# I2C_4CH_PWM_MODULE.net
KiCad netlist of a schematic drawn in EAGLE
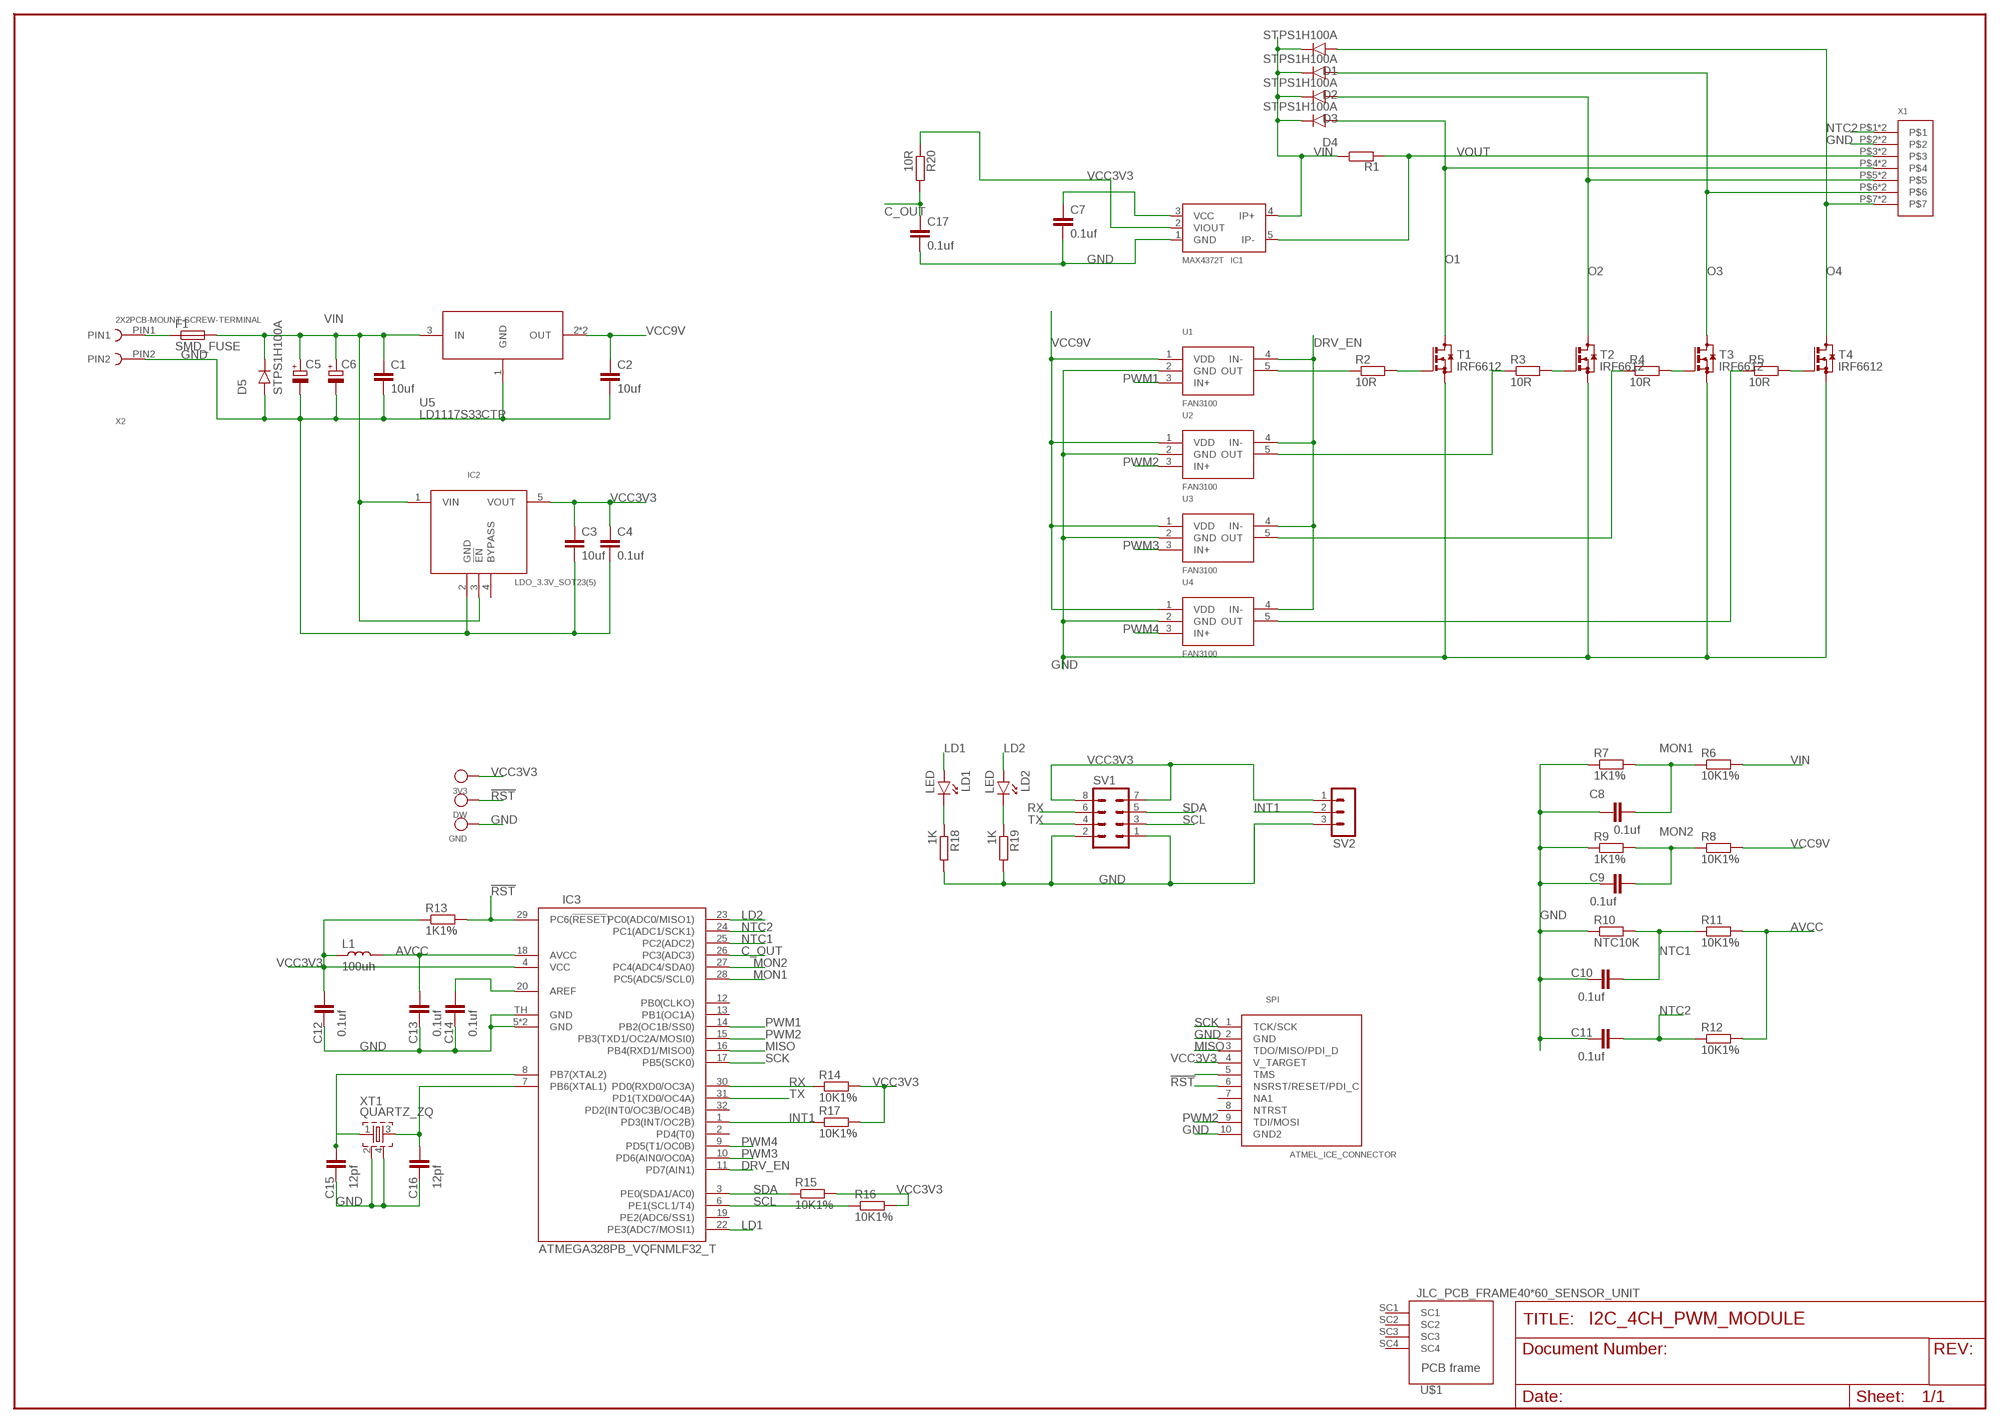
[diagram p0: schematic, sheet 1]

(export (version "E")
  (design (tool "Eeschema 10.0.6"))
  (components
    (comp (ref "3V3")
      (value "TEST_POINT_D2MM")
      (footprint "eagle-import:TP")
      (libsource (lib "eagle-import") (part "TEST_POINT_D2MM"))
    )
    (comp (ref "C1")
      (value "10uf")
      (footprint "eagle-import:1206")
      (libsource (lib "eagle-import") (part "SMD_C1206"))
    )
    (comp (ref "C2")
      (value "10uf")
      (footprint "eagle-import:1206")
      (libsource (lib "eagle-import") (part "SMD_C1206"))
    )
    (comp (ref "C3")
      (value "10uf")
      (footprint "eagle-import:1206")
      (libsource (lib "eagle-import") (part "SMD_C1206"))
    )
    (comp (ref "C4")
      (value "0.1uf")
      (footprint "eagle-import:0603")
      (libsource (lib "eagle-import") (part "SMD_C0603"))
    )
    (comp (ref "C5")
      (value "CPOL-EU153CLV-0605")
      (footprint "eagle-import:153CLV-0605")
      (libsource (lib "eagle-import") (part "CPOL-EU153CLV-0605"))
    )
    (comp (ref "C6")
      (value "CPOL-EU153CLV-0605")
      (footprint "eagle-import:153CLV-0605")
      (libsource (lib "eagle-import") (part "CPOL-EU153CLV-0605"))
    )
    (comp (ref "C7")
      (value "0.1uf")
      (footprint "eagle-import:0603")
      (libsource (lib "eagle-import") (part "SMD_C0603"))
    )
    (comp (ref "C8")
      (value "0.1uf")
      (footprint "eagle-import:0603")
      (libsource (lib "eagle-import") (part "SMD_C0603"))
    )
    (comp (ref "C9")
      (value "0.1uf")
      (footprint "eagle-import:0603")
      (libsource (lib "eagle-import") (part "SMD_C0603"))
    )
    (comp (ref "C10")
      (value "0.1uf")
      (footprint "eagle-import:0603")
      (libsource (lib "eagle-import") (part "SMD_C0603"))
    )
    (comp (ref "C11")
      (value "0.1uf")
      (footprint "eagle-import:0603")
      (libsource (lib "eagle-import") (part "SMD_C0603"))
    )
    (comp (ref "C12")
      (value "0.1uf")
      (footprint "eagle-import:0603")
      (libsource (lib "eagle-import") (part "SMD_C0603"))
    )
    (comp (ref "C13")
      (value "0.1uf")
      (footprint "eagle-import:0603")
      (libsource (lib "eagle-import") (part "SMD_C0603"))
    )
    (comp (ref "C14")
      (value "0.1uf")
      (footprint "eagle-import:0603")
      (libsource (lib "eagle-import") (part "SMD_C0603"))
    )
    (comp (ref "C15")
      (value "12pf")
      (footprint "eagle-import:0603")
      (libsource (lib "eagle-import") (part "SMD_C0603"))
    )
    (comp (ref "C16")
      (value "12pf")
      (footprint "eagle-import:0603")
      (libsource (lib "eagle-import") (part "SMD_C0603"))
    )
    (comp (ref "C17")
      (value "0.1uf")
      (footprint "eagle-import:0603")
      (libsource (lib "eagle-import") (part "SMD_C0603"))
    )
    (comp (ref "D1")
      (value "STPS1H100A")
      (footprint "eagle-import:SMA403D")
      (libsource (lib "eagle-import") (part "STPS1H100A"))
    )
    (comp (ref "D2")
      (value "STPS1H100A")
      (footprint "eagle-import:SMA403D")
      (libsource (lib "eagle-import") (part "STPS1H100A"))
    )
    (comp (ref "D3")
      (value "STPS1H100A")
      (footprint "eagle-import:SMA403D")
      (libsource (lib "eagle-import") (part "STPS1H100A"))
    )
    (comp (ref "D4")
      (value "STPS1H100A")
      (footprint "eagle-import:SMA403D")
      (libsource (lib "eagle-import") (part "STPS1H100A"))
    )
    (comp (ref "D5")
      (value "STPS1H100A")
      (footprint "eagle-import:SMA403D")
      (libsource (lib "eagle-import") (part "STPS1H100A"))
    )
    (comp (ref "DW")
      (value "TEST_POINT_D2MM")
      (footprint "eagle-import:TP")
      (libsource (lib "eagle-import") (part "TEST_POINT_D2MM"))
    )
    (comp (ref "F1")
      (value "SMD_FUSE")
      (footprint "eagle-import:SMD_2410_FUSE_NOK")
      (libsource (lib "eagle-import") (part "SMD_FUSE"))
    )
    (comp (ref "GND")
      (value "TEST_POINT_D2MM")
      (footprint "eagle-import:TP")
      (libsource (lib "eagle-import") (part "TEST_POINT_D2MM"))
    )
    (comp (ref "IC1")
      (value "MAX4372T")
      (footprint "eagle-import:SOT-23(5)")
      (libsource (lib "eagle-import") (part "MAX4372T"))
    )
    (comp (ref "IC2")
      (value "LDO_3.3V_SOT23(5)")
      (footprint "eagle-import:SOT-23(5)")
      (libsource (lib "eagle-import") (part "LDO_3.3V_SOT23(5)"))
    )
    (comp (ref "IC3")
      (value "ATMEGA328PB_VQFNMLF32_T")
      (footprint "eagle-import:MLF32-TH")
      (libsource (lib "eagle-import") (part "ATMEGA328PB_VQFNMLF32_T"))
    )
    (comp (ref "L1")
      (value "100uh")
      (footprint "eagle-import:0603")
      (libsource (lib "eagle-import") (part "SMD_L0603"))
    )
    (comp (ref "LD1")
      (value "LED")
      (footprint "eagle-import:3MM_DIP_LED")
      (libsource (lib "eagle-import") (part "LED"))
    )
    (comp (ref "LD2")
      (value "LED")
      (footprint "eagle-import:3MM_DIP_LED")
      (libsource (lib "eagle-import") (part "LED"))
    )
    (comp (ref "R1")
      (value "SMS-0")
      (footprint "eagle-import:SMS-0")
      (libsource (lib "eagle-import") (part "SMS-0"))
    )
    (comp (ref "R2")
      (value "10R")
      (footprint "eagle-import:0603")
      (libsource (lib "eagle-import") (part "SMD_R0603"))
    )
    (comp (ref "R3")
      (value "10R")
      (footprint "eagle-import:0603")
      (libsource (lib "eagle-import") (part "SMD_R0603"))
    )
    (comp (ref "R4")
      (value "10R")
      (footprint "eagle-import:0603")
      (libsource (lib "eagle-import") (part "SMD_R0603"))
    )
    (comp (ref "R5")
      (value "10R")
      (footprint "eagle-import:0603")
      (libsource (lib "eagle-import") (part "SMD_R0603"))
    )
    (comp (ref "R6")
      (value "10K1%")
      (footprint "eagle-import:0603")
      (libsource (lib "eagle-import") (part "SMD_R0603"))
    )
    (comp (ref "R7")
      (value "1K1%")
      (footprint "eagle-import:0603")
      (libsource (lib "eagle-import") (part "SMD_R0603"))
    )
    (comp (ref "R8")
      (value "10K1%")
      (footprint "eagle-import:0603")
      (libsource (lib "eagle-import") (part "SMD_R0603"))
    )
    (comp (ref "R9")
      (value "1K1%")
      (footprint "eagle-import:0603")
      (libsource (lib "eagle-import") (part "SMD_R0603"))
    )
    (comp (ref "R10")
      (value "NTC10K")
      (footprint "eagle-import:0603")
      (libsource (lib "eagle-import") (part "SMD_R0603"))
    )
    (comp (ref "R11")
      (value "10K1%")
      (footprint "eagle-import:0603")
      (libsource (lib "eagle-import") (part "SMD_R0603"))
    )
    (comp (ref "R12")
      (value "10K1%")
      (footprint "eagle-import:0603")
      (libsource (lib "eagle-import") (part "SMD_R0603"))
    )
    (comp (ref "R13")
      (value "1K1%")
      (footprint "eagle-import:0603")
      (libsource (lib "eagle-import") (part "SMD_R0603"))
    )
    (comp (ref "R14")
      (value "10K1%")
      (footprint "eagle-import:0603")
      (libsource (lib "eagle-import") (part "SMD_R0603"))
    )
    (comp (ref "R15")
      (value "10K1%")
      (footprint "eagle-import:0603")
      (libsource (lib "eagle-import") (part "SMD_R0603"))
    )
    (comp (ref "R16")
      (value "10K1%")
      (footprint "eagle-import:0603")
      (libsource (lib "eagle-import") (part "SMD_R0603"))
    )
    (comp (ref "R17")
      (value "10K1%")
      (footprint "eagle-import:0603")
      (libsource (lib "eagle-import") (part "SMD_R0603"))
    )
    (comp (ref "R18")
      (value "1K")
      (footprint "eagle-import:0603")
      (libsource (lib "eagle-import") (part "SMD_R0603"))
    )
    (comp (ref "R19")
      (value "1K")
      (footprint "eagle-import:0603")
      (libsource (lib "eagle-import") (part "SMD_R0603"))
    )
    (comp (ref "R20")
      (value "10R")
      (footprint "eagle-import:0603")
      (libsource (lib "eagle-import") (part "SMD_R0603"))
    )
    (comp (ref "SPI")
      (value "ATMEL_ICE_CONNECTOR")
      (footprint "eagle-import:MINI10P_SPI_JTAG_PDI")
      (libsource (lib "eagle-import") (part "ATMEL_ICE_CONNECTOR"))
    )
    (comp (ref "SV1")
      (value "MA04-2")
      (footprint "eagle-import:MA04-2")
      (libsource (lib "eagle-import") (part "MA04-2"))
    )
    (comp (ref "SV2")
      (value "MA03-1")
      (footprint "eagle-import:MA03-1")
      (libsource (lib "eagle-import") (part "MA03-1"))
    )
    (comp (ref "T1")
      (value "IRF6612")
      (footprint "eagle-import:DIRECTFET_IRF6612")
      (libsource (lib "eagle-import") (part "IRF6612"))
    )
    (comp (ref "T2")
      (value "IRF6612")
      (footprint "eagle-import:DIRECTFET_IRF6612")
      (libsource (lib "eagle-import") (part "IRF6612"))
    )
    (comp (ref "T3")
      (value "IRF6612")
      (footprint "eagle-import:DIRECTFET_IRF6612")
      (libsource (lib "eagle-import") (part "IRF6612"))
    )
    (comp (ref "T4")
      (value "IRF6612")
      (footprint "eagle-import:DIRECTFET_IRF6612")
      (libsource (lib "eagle-import") (part "IRF6612"))
    )
    (comp (ref "U$1")
      (value "JLC_PCB_FRAME40*60_SENSOR_UNIT")
      (footprint "eagle-import:40X60_SENSOR_UNIT")
      (libsource (lib "eagle-import") (part "JLC_PCB_FRAME4060_SENSOR_UNIT"))
    )
    (comp (ref "U1")
      (value "FAN3100")
      (footprint "eagle-import:SOT-23(5)")
      (libsource (lib "eagle-import") (part "FAN3100"))
    )
    (comp (ref "U2")
      (value "FAN3100")
      (footprint "eagle-import:SOT-23(5)")
      (libsource (lib "eagle-import") (part "FAN3100"))
    )
    (comp (ref "U3")
      (value "FAN3100")
      (footprint "eagle-import:SOT-23(5)")
      (libsource (lib "eagle-import") (part "FAN3100"))
    )
    (comp (ref "U4")
      (value "FAN3100")
      (footprint "eagle-import:SOT-23(5)")
      (libsource (lib "eagle-import") (part "FAN3100"))
    )
    (comp (ref "U5")
      (value "LD1117S33CTR")
      (footprint "eagle-import:SOT223")
      (fields (field (name "MF") "STMicroelectronics"))
      (libsource (lib "eagle-import") (part "LD1117S33CTR"))
    )
    (comp (ref "X1")
      (value "WAGO250_X7")
      (footprint "eagle-import:WAGO250_FP_7X")
      (libsource (lib "eagle-import") (part "WAGO250_X7"))
    )
    (comp (ref "X2")
      (value "2X2PCB-MOUNT-SCREW-TERMINAL")
      (footprint "eagle-import:2X2PCB-MOUNT-SCREW-TERMINAL")
      (libsource (lib "eagle-import") (part "2X2PCB-MOUNT-SCREW-TERMINAL"))
    )
    (comp (ref "XT1")
      (value "QUARTZ_ZQ")
      (footprint "eagle-import:QUARTZ_3X3MM")
      (libsource (lib "eagle-import") (part "QUARTZ_ZQ"))
    )
  )
  (nets
    (net (code "1") (name "/AVCC") (class "Default")
      (node (ref "C13") (pin "2") (pinfunction "2_2") (pintype "passive"))
      (node (ref "IC3") (pin "18") (pinfunction "AVCC_18") (pintype "power_in"))
      (node (ref "L1") (pin "2") (pinfunction "2_2") (pintype "passive"))
      (node (ref "R11") (pin "2") (pinfunction "2_2") (pintype "passive"))
      (node (ref "R12") (pin "2") (pinfunction "2_2") (pintype "passive"))
    )
    (net (code "2") (name "/C_OUT") (class "Default")
      (node (ref "C17") (pin "1") (pinfunction "1_1") (pintype "passive"))
      (node (ref "IC3") (pin "26") (pinfunction "PC3(ADC3)_26") (pintype "bidirectional"))
      (node (ref "R20") (pin "2") (pinfunction "2_2") (pintype "passive"))
    )
    (net (code "3") (name "/DRV_EN") (class "Default")
      (node (ref "IC3") (pin "11") (pinfunction "PD7(AIN1)_11") (pintype "bidirectional"))
      (node (ref "U1") (pin "4") (pinfunction "IN-_4") (pintype "bidirectional"))
      (node (ref "U2") (pin "4") (pinfunction "IN-_4") (pintype "bidirectional"))
      (node (ref "U3") (pin "4") (pinfunction "IN-_4") (pintype "bidirectional"))
      (node (ref "U4") (pin "4") (pinfunction "IN-_4") (pintype "bidirectional"))
    )
    (net (code "4") (name "/GND") (class "Default")
      (node (ref "C1") (pin "2") (pinfunction "2_2") (pintype "passive"))
      (node (ref "C10") (pin "1") (pinfunction "1_1") (pintype "passive"))
      (node (ref "C11") (pin "1") (pinfunction "1_1") (pintype "passive"))
      (node (ref "C12") (pin "1") (pinfunction "1_1") (pintype "passive"))
      (node (ref "C13") (pin "1") (pinfunction "1_1") (pintype "passive"))
      (node (ref "C14") (pin "1") (pinfunction "1_1") (pintype "passive"))
      (node (ref "C15") (pin "1") (pinfunction "1_1") (pintype "passive"))
      (node (ref "C16") (pin "1") (pinfunction "1_1") (pintype "passive"))
      (node (ref "C17") (pin "2") (pinfunction "2_2") (pintype "passive"))
      (node (ref "C2") (pin "2") (pinfunction "2_2") (pintype "passive"))
      (node (ref "C3") (pin "2") (pinfunction "2_2") (pintype "passive"))
      (node (ref "C4") (pin "2") (pinfunction "2_2") (pintype "passive"))
      (node (ref "C5") (pin "-") (pinfunction "-_-") (pintype "passive"))
      (node (ref "C6") (pin "-") (pinfunction "-_-") (pintype "passive"))
      (node (ref "C7") (pin "2") (pinfunction "2_2") (pintype "passive"))
      (node (ref "C8") (pin "1") (pinfunction "1_1") (pintype "passive"))
      (node (ref "C9") (pin "1") (pinfunction "1_1") (pintype "passive"))
      (node (ref "D5") (pin "P$2") (pinfunction "A_P$2") (pintype "bidirectional"))
      (node (ref "GND") (pin "P$1") (pinfunction "1_P$1") (pintype "bidirectional"))
      (node (ref "IC1") (pin "1") (pinfunction "GND_1") (pintype "bidirectional"))
      (node (ref "IC2") (pin "2") (pinfunction "GND_2") (pintype "bidirectional"))
      (node (ref "IC3") (pin "21") (pinfunction "GND_21") (pintype "power_in"))
      (node (ref "IC3") (pin "5") (pinfunction "GND_5") (pintype "power_in"))
      (node (ref "IC3") (pin "TH") (pinfunction "GND_TH") (pintype "power_in"))
      (node (ref "R10") (pin "1") (pinfunction "1_1") (pintype "passive"))
      (node (ref "R18") (pin "2") (pinfunction "2_2") (pintype "passive"))
      (node (ref "R19") (pin "2") (pinfunction "2_2") (pintype "passive"))
      (node (ref "R7") (pin "1") (pinfunction "1_1") (pintype "passive"))
      (node (ref "R9") (pin "1") (pinfunction "1_1") (pintype "passive"))
      (node (ref "SPI") (pin "10") (pinfunction "GND2_10") (pintype "bidirectional"))
      (node (ref "SPI") (pin "2") (pinfunction "GND_2") (pintype "bidirectional"))
      (node (ref "SV1") (pin "1") (pinfunction "1_1") (pintype "passive"))
      (node (ref "SV1") (pin "2") (pinfunction "2_2") (pintype "passive"))
      (node (ref "SV2") (pin "3") (pinfunction "3_3") (pintype "passive"))
      (node (ref "T1") (pin "S1") (pinfunction "S_S1") (pintype "passive"))
      (node (ref "T1") (pin "S2") (pinfunction "S_S2") (pintype "passive"))
      (node (ref "T2") (pin "S1") (pinfunction "S_S1") (pintype "passive"))
      (node (ref "T2") (pin "S2") (pinfunction "S_S2") (pintype "passive"))
      (node (ref "T3") (pin "S1") (pinfunction "S_S1") (pintype "passive"))
      (node (ref "T3") (pin "S2") (pinfunction "S_S2") (pintype "passive"))
      (node (ref "T4") (pin "S1") (pinfunction "S_S1") (pintype "passive"))
      (node (ref "T4") (pin "S2") (pinfunction "S_S2") (pintype "passive"))
      (node (ref "U1") (pin "2") (pinfunction "GND_2") (pintype "bidirectional"))
      (node (ref "U2") (pin "2") (pinfunction "GND_2") (pintype "bidirectional"))
      (node (ref "U3") (pin "2") (pinfunction "GND_2") (pintype "bidirectional"))
      (node (ref "U4") (pin "2") (pinfunction "GND_2") (pintype "bidirectional"))
      (node (ref "U5") (pin "1") (pinfunction "GND_1") (pintype "passive"))
      (node (ref "X1") (pin "P$2") (pinfunction "P$2_P$2") (pintype "bidirectional"))
      (node (ref "X1") (pin "U$2") (pinfunction "P$2_U$2") (pintype "bidirectional"))
      (node (ref "X2") (pin "PIN2") (pinfunction "PIN2_PIN2") (pintype "bidirectional"))
      (node (ref "XT1") (pin "2") (pinfunction "2_2") (pintype "passive"))
      (node (ref "XT1") (pin "4") (pinfunction "4_4") (pintype "passive"))
    )
    (net (code "5") (name "/INT1") (class "Default")
      (node (ref "IC3") (pin "1") (pinfunction "PD3(INT/OC2B)_1") (pintype "bidirectional"))
      (node (ref "R17") (pin "1") (pinfunction "1_1") (pintype "passive"))
      (node (ref "SV2") (pin "2") (pinfunction "2_2") (pintype "passive"))
    )
    (net (code "6") (name "/LD1") (class "Default")
      (node (ref "IC3") (pin "22") (pinfunction "PE3(ADC7/MOSI1)_22") (pintype "bidirectional"))
      (node (ref "LD1") (pin "A") (pinfunction "A_A") (pintype "bidirectional"))
    )
    (net (code "7") (name "/LD2") (class "Default")
      (node (ref "IC3") (pin "23") (pinfunction "PC0(ADC0/MISO1)_23") (pintype "bidirectional"))
      (node (ref "LD2") (pin "A") (pinfunction "A_A") (pintype "bidirectional"))
    )
    (net (code "8") (name "/MISO") (class "Default")
      (node (ref "IC3") (pin "16") (pinfunction "PB4(RXD1/MISO0)_16") (pintype "bidirectional"))
      (node (ref "SPI") (pin "3") (pinfunction "TDO/MISO/PDI_D_3") (pintype "bidirectional"))
    )
    (net (code "9") (name "/MON1") (class "Default")
      (node (ref "C8") (pin "2") (pinfunction "2_2") (pintype "passive"))
      (node (ref "IC3") (pin "28") (pinfunction "PC5(ADC5/SCL0)_28") (pintype "bidirectional"))
      (node (ref "R6") (pin "1") (pinfunction "1_1") (pintype "passive"))
      (node (ref "R7") (pin "2") (pinfunction "2_2") (pintype "passive"))
    )
    (net (code "10") (name "/MON2") (class "Default")
      (node (ref "C9") (pin "2") (pinfunction "2_2") (pintype "passive"))
      (node (ref "IC3") (pin "27") (pinfunction "PC4(ADC4/SDA0)_27") (pintype "bidirectional"))
      (node (ref "R8") (pin "1") (pinfunction "1_1") (pintype "passive"))
      (node (ref "R9") (pin "2") (pinfunction "2_2") (pintype "passive"))
    )
    (net (code "11") (name "/NTC1") (class "Default")
      (node (ref "C10") (pin "2") (pinfunction "2_2") (pintype "passive"))
      (node (ref "IC3") (pin "25") (pinfunction "PC2(ADC2)_25") (pintype "bidirectional"))
      (node (ref "R10") (pin "2") (pinfunction "2_2") (pintype "passive"))
      (node (ref "R11") (pin "1") (pinfunction "1_1") (pintype "passive"))
    )
    (net (code "12") (name "/NTC2") (class "Default")
      (node (ref "C11") (pin "2") (pinfunction "2_2") (pintype "passive"))
      (node (ref "IC3") (pin "24") (pinfunction "PC1(ADC1/SCK1)_24") (pintype "bidirectional"))
      (node (ref "R12") (pin "1") (pinfunction "1_1") (pintype "passive"))
      (node (ref "X1") (pin "P$1") (pinfunction "P$1_P$1") (pintype "bidirectional"))
      (node (ref "X1") (pin "U$1") (pinfunction "P$1_U$1") (pintype "bidirectional"))
    )
    (net (code "13") (name "/O1") (class "Default")
      (node (ref "D4") (pin "P$2") (pinfunction "A_P$2") (pintype "bidirectional"))
      (node (ref "T1") (pin "D1") (pinfunction "D_D1") (pintype "passive"))
      (node (ref "T1") (pin "D2") (pinfunction "D_D2") (pintype "passive"))
      (node (ref "X1") (pin "P$4") (pinfunction "P$4_P$4") (pintype "bidirectional"))
      (node (ref "X1") (pin "U$4") (pinfunction "P$4_U$4") (pintype "bidirectional"))
    )
    (net (code "14") (name "/O2") (class "Default")
      (node (ref "D3") (pin "P$2") (pinfunction "A_P$2") (pintype "bidirectional"))
      (node (ref "T2") (pin "D1") (pinfunction "D_D1") (pintype "passive"))
      (node (ref "T2") (pin "D2") (pinfunction "D_D2") (pintype "passive"))
      (node (ref "X1") (pin "P$5") (pinfunction "P$5_P$5") (pintype "bidirectional"))
      (node (ref "X1") (pin "U$5") (pinfunction "P$5_U$5") (pintype "bidirectional"))
    )
    (net (code "15") (name "/O3") (class "Default")
      (node (ref "D2") (pin "P$2") (pinfunction "A_P$2") (pintype "bidirectional"))
      (node (ref "T3") (pin "D1") (pinfunction "D_D1") (pintype "passive"))
      (node (ref "T3") (pin "D2") (pinfunction "D_D2") (pintype "passive"))
      (node (ref "X1") (pin "P$6") (pinfunction "P$6_P$6") (pintype "bidirectional"))
      (node (ref "X1") (pin "U$6") (pinfunction "P$6_U$6") (pintype "bidirectional"))
    )
    (net (code "16") (name "/O4") (class "Default")
      (node (ref "D1") (pin "P$2") (pinfunction "A_P$2") (pintype "bidirectional"))
      (node (ref "T4") (pin "D1") (pinfunction "D_D1") (pintype "passive"))
      (node (ref "T4") (pin "D2") (pinfunction "D_D2") (pintype "passive"))
      (node (ref "X1") (pin "P$7") (pinfunction "P$7_P$7") (pintype "bidirectional"))
      (node (ref "X1") (pin "U$7") (pinfunction "P$7_U$7") (pintype "bidirectional"))
    )
    (net (code "17") (name "/PWM1") (class "Default")
      (node (ref "IC3") (pin "14") (pinfunction "PB2(OC1B/SS0)_14") (pintype "bidirectional"))
      (node (ref "U1") (pin "3") (pinfunction "IN+_3") (pintype "bidirectional"))
    )
    (net (code "18") (name "/PWM2") (class "Default")
      (node (ref "IC3") (pin "15") (pinfunction "PB3(TXD1/OC2A/MOSI0)_15") (pintype "bidirectional"))
      (node (ref "SPI") (pin "9") (pinfunction "TDI/MOSI_9") (pintype "bidirectional"))
      (node (ref "U2") (pin "3") (pinfunction "IN+_3") (pintype "bidirectional"))
    )
    (net (code "19") (name "/PWM3") (class "Default")
      (node (ref "IC3") (pin "10") (pinfunction "PD6(AIN0/OC0A)_10") (pintype "bidirectional"))
      (node (ref "U3") (pin "3") (pinfunction "IN+_3") (pintype "bidirectional"))
    )
    (net (code "20") (name "/PWM4") (class "Default")
      (node (ref "IC3") (pin "9") (pinfunction "PD5(T1/OC0B)_9") (pintype "bidirectional"))
      (node (ref "U4") (pin "3") (pinfunction "IN+_3") (pintype "bidirectional"))
    )
    (net (code "21") (name "/RX") (class "Default")
      (node (ref "IC3") (pin "30") (pinfunction "PD0(RXD0/OC3A)_30") (pintype "bidirectional"))
      (node (ref "R14") (pin "1") (pinfunction "1_1") (pintype "passive"))
      (node (ref "SV1") (pin "6") (pinfunction "6_6") (pintype "passive"))
    )
    (net (code "22") (name "/SCK") (class "Default")
      (node (ref "IC3") (pin "17") (pinfunction "PB5(SCK0)_17") (pintype "bidirectional"))
      (node (ref "SPI") (pin "1") (pinfunction "TCK/SCK_1") (pintype "bidirectional"))
    )
    (net (code "23") (name "/SCL") (class "Default")
      (node (ref "IC3") (pin "6") (pinfunction "PE1(SCL1/T4)_6") (pintype "bidirectional"))
      (node (ref "R16") (pin "1") (pinfunction "1_1") (pintype "passive"))
      (node (ref "SV1") (pin "3") (pinfunction "3_3") (pintype "passive"))
    )
    (net (code "24") (name "/SDA") (class "Default")
      (node (ref "IC3") (pin "3") (pinfunction "PE0(SDA1/AC0)_3") (pintype "bidirectional"))
      (node (ref "R15") (pin "1") (pinfunction "1_1") (pintype "passive"))
      (node (ref "SV1") (pin "5") (pinfunction "5_5") (pintype "passive"))
    )
    (net (code "25") (name "/TX") (class "Default")
      (node (ref "IC3") (pin "31") (pinfunction "PD1(TXD0/OC4A)_31") (pintype "bidirectional"))
      (node (ref "SV1") (pin "4") (pinfunction "4_4") (pintype "passive"))
    )
    (net (code "26") (name "/VCC3V3") (class "Default")
      (node (ref "3V3") (pin "P$1") (pinfunction "1_P$1") (pintype "bidirectional"))
      (node (ref "C12") (pin "2") (pinfunction "2_2") (pintype "passive"))
      (node (ref "C3") (pin "1") (pinfunction "1_1") (pintype "passive"))
      (node (ref "C4") (pin "1") (pinfunction "1_1") (pintype "passive"))
      (node (ref "C7") (pin "1") (pinfunction "1_1") (pintype "passive"))
      (node (ref "IC1") (pin "3") (pinfunction "VCC_3") (pintype "bidirectional"))
      (node (ref "IC2") (pin "5") (pinfunction "VOUT_5") (pintype "bidirectional"))
      (node (ref "IC3") (pin "4") (pinfunction "VCC_4") (pintype "power_in"))
      (node (ref "L1") (pin "1") (pinfunction "1_1") (pintype "passive"))
      (node (ref "R13") (pin "1") (pinfunction "1_1") (pintype "passive"))
      (node (ref "R14") (pin "2") (pinfunction "2_2") (pintype "passive"))
      (node (ref "R15") (pin "2") (pinfunction "2_2") (pintype "passive"))
      (node (ref "R16") (pin "2") (pinfunction "2_2") (pintype "passive"))
      (node (ref "R17") (pin "2") (pinfunction "2_2") (pintype "passive"))
      (node (ref "SPI") (pin "4") (pinfunction "V_TARGET_4") (pintype "bidirectional"))
      (node (ref "SV1") (pin "7") (pinfunction "7_7") (pintype "passive"))
      (node (ref "SV1") (pin "8") (pinfunction "8_8") (pintype "passive"))
      (node (ref "SV2") (pin "1") (pinfunction "1_1") (pintype "passive"))
    )
    (net (code "27") (name "/VCC9V") (class "Default")
      (node (ref "C2") (pin "1") (pinfunction "1_1") (pintype "passive"))
      (node (ref "R8") (pin "2") (pinfunction "2_2") (pintype "passive"))
      (node (ref "U1") (pin "1") (pinfunction "VDD_1") (pintype "bidirectional"))
      (node (ref "U2") (pin "1") (pinfunction "VDD_1") (pintype "bidirectional"))
      (node (ref "U3") (pin "1") (pinfunction "VDD_1") (pintype "bidirectional"))
      (node (ref "U4") (pin "1") (pinfunction "VDD_1") (pintype "bidirectional"))
      (node (ref "U5") (pin "2") (pinfunction "OUT_2") (pintype "output"))
      (node (ref "U5") (pin "4") (pinfunction "OUT_4") (pintype "output"))
    )
    (net (code "28") (name "/VIN") (class "Default")
      (node (ref "C1") (pin "1") (pinfunction "1_1") (pintype "passive"))
      (node (ref "C5") (pin "+") (pinfunction "+_+") (pintype "passive"))
      (node (ref "C6") (pin "+") (pinfunction "+_+") (pintype "passive"))
      (node (ref "D1") (pin "P$1") (pinfunction "C_P$1") (pintype "bidirectional"))
      (node (ref "D2") (pin "P$1") (pinfunction "C_P$1") (pintype "bidirectional"))
      (node (ref "D3") (pin "P$1") (pinfunction "C_P$1") (pintype "bidirectional"))
      (node (ref "D4") (pin "P$1") (pinfunction "C_P$1") (pintype "bidirectional"))
      (node (ref "D5") (pin "P$1") (pinfunction "C_P$1") (pintype "bidirectional"))
      (node (ref "F1") (pin "P$2") (pinfunction "2_P$2") (pintype "passive"))
      (node (ref "IC1") (pin "4") (pinfunction "IP+_4") (pintype "bidirectional"))
      (node (ref "IC2") (pin "1") (pinfunction "VIN_1") (pintype "bidirectional"))
      (node (ref "IC2") (pin "3") (pinfunction "~{EN}_3") (pintype "bidirectional"))
      (node (ref "R1") (pin "1") (pinfunction "1_1") (pintype "passive"))
      (node (ref "R6") (pin "2") (pinfunction "2_2") (pintype "passive"))
      (node (ref "U5") (pin "3") (pinfunction "IN_3") (pintype "input"))
    )
    (net (code "29") (name "/VOUT") (class "Default")
      (node (ref "IC1") (pin "5") (pinfunction "IP-_5") (pintype "bidirectional"))
      (node (ref "R1") (pin "2") (pinfunction "2_2") (pintype "passive"))
      (node (ref "X1") (pin "P$3") (pinfunction "P$3_P$3") (pintype "bidirectional"))
      (node (ref "X1") (pin "U$3") (pinfunction "P$3_U$3") (pintype "bidirectional"))
    )
    (net (code "30") (name "/~{RST}") (class "Default")
      (node (ref "DW") (pin "P$1") (pinfunction "1_P$1") (pintype "bidirectional"))
      (node (ref "IC3") (pin "29") (pinfunction "PC6(~{RESET})_29") (pintype "bidirectional"))
      (node (ref "R13") (pin "2") (pinfunction "2_2") (pintype "passive"))
      (node (ref "SPI") (pin "6") (pinfunction "NSRST/RESET/PDI_C_6") (pintype "bidirectional"))
    )
    (net (code "31") (name "Net-(F1-1)") (class "Default")
      (node (ref "F1") (pin "P$1") (pinfunction "1_P$1") (pintype "passive"))
      (node (ref "X2") (pin "PIN1") (pinfunction "PIN1_PIN1") (pintype "bidirectional"))
    )
    (net (code "32") (name "Net-(IC1-VIOUT)") (class "Default")
      (node (ref "IC1") (pin "2") (pinfunction "VIOUT_2") (pintype "bidirectional"))
      (node (ref "R20") (pin "1") (pinfunction "1_1") (pintype "passive"))
    )
    (net (code "33") (name "Net-(IC3-AREF)") (class "Default")
      (node (ref "C14") (pin "2") (pinfunction "2_2") (pintype "passive"))
      (node (ref "IC3") (pin "20") (pinfunction "AREF_20") (pintype "passive"))
    )
    (net (code "34") (name "Net-(IC3-PB6(XTAL1))") (class "Default")
      (node (ref "C16") (pin "2") (pinfunction "2_2") (pintype "passive"))
      (node (ref "IC3") (pin "7") (pinfunction "PB6(XTAL1)_7") (pintype "bidirectional"))
      (node (ref "XT1") (pin "3") (pinfunction "3_3") (pintype "passive"))
    )
    (net (code "35") (name "Net-(IC3-PB7(XTAL2))") (class "Default")
      (node (ref "C15") (pin "2") (pinfunction "2_2") (pintype "passive"))
      (node (ref "IC3") (pin "8") (pinfunction "PB7(XTAL2)_8") (pintype "bidirectional"))
      (node (ref "XT1") (pin "1") (pinfunction "1_1") (pintype "passive"))
    )
    (net (code "36") (name "Net-(LD1-PadK)") (class "Default")
      (node (ref "LD1") (pin "K") (pinfunction "K_K") (pintype "bidirectional"))
      (node (ref "R18") (pin "1") (pinfunction "1_1") (pintype "passive"))
    )
    (net (code "37") (name "Net-(LD2-PadK)") (class "Default")
      (node (ref "LD2") (pin "K") (pinfunction "K_K") (pintype "bidirectional"))
      (node (ref "R19") (pin "1") (pinfunction "1_1") (pintype "passive"))
    )
    (net (code "38") (name "Net-(R2-Pad2)") (class "Default")
      (node (ref "R2") (pin "2") (pinfunction "2_2") (pintype "passive"))
      (node (ref "T1") (pin "G") (pinfunction "G_G") (pintype "passive"))
    )
    (net (code "39") (name "Net-(R3-Pad2)") (class "Default")
      (node (ref "R3") (pin "2") (pinfunction "2_2") (pintype "passive"))
      (node (ref "T2") (pin "G") (pinfunction "G_G") (pintype "passive"))
    )
    (net (code "40") (name "Net-(R4-Pad2)") (class "Default")
      (node (ref "R4") (pin "2") (pinfunction "2_2") (pintype "passive"))
      (node (ref "T3") (pin "G") (pinfunction "G_G") (pintype "passive"))
    )
    (net (code "41") (name "Net-(R5-Pad2)") (class "Default")
      (node (ref "R5") (pin "2") (pinfunction "2_2") (pintype "passive"))
      (node (ref "T4") (pin "G") (pinfunction "G_G") (pintype "passive"))
    )
    (net (code "42") (name "Net-(U1-OUT)") (class "Default")
      (node (ref "R2") (pin "1") (pinfunction "1_1") (pintype "passive"))
      (node (ref "U1") (pin "5") (pinfunction "OUT_5") (pintype "bidirectional"))
    )
    (net (code "43") (name "Net-(U2-OUT)") (class "Default")
      (node (ref "R3") (pin "1") (pinfunction "1_1") (pintype "passive"))
      (node (ref "U2") (pin "5") (pinfunction "OUT_5") (pintype "bidirectional"))
    )
    (net (code "44") (name "Net-(U3-OUT)") (class "Default")
      (node (ref "R4") (pin "1") (pinfunction "1_1") (pintype "passive"))
      (node (ref "U3") (pin "5") (pinfunction "OUT_5") (pintype "bidirectional"))
    )
    (net (code "45") (name "Net-(U4-OUT)") (class "Default")
      (node (ref "R5") (pin "1") (pinfunction "1_1") (pintype "passive"))
      (node (ref "U4") (pin "5") (pinfunction "OUT_5") (pintype "bidirectional"))
    )
    (net (code "46") (name "unconnected-(IC2-BYPASS-Pad4)") (class "Default")
      (node (ref "IC2") (pin "4") (pinfunction "BYPASS_4") (pintype "bidirectional"))
    )
    (net (code "47") (name "unconnected-(IC3-PB0(CLKO)-Pad12)") (class "Default")
      (node (ref "IC3") (pin "12") (pinfunction "PB0(CLKO)_12") (pintype "bidirectional"))
    )
    (net (code "48") (name "unconnected-(IC3-PB1(OC1A)-Pad13)") (class "Default")
      (node (ref "IC3") (pin "13") (pinfunction "PB1(OC1A)_13") (pintype "bidirectional"))
    )
    (net (code "49") (name "unconnected-(IC3-PD2(INT0{slash}OC3B{slash}OC4B)-Pad32)") (class "Default")
      (node (ref "IC3") (pin "32") (pinfunction "PD2(INT0/OC3B/OC4B)_32") (pintype "bidirectional"))
    )
    (net (code "50") (name "unconnected-(IC3-PD4(T0)-Pad2)") (class "Default")
      (node (ref "IC3") (pin "2") (pinfunction "PD4(T0)_2") (pintype "bidirectional"))
    )
    (net (code "51") (name "unconnected-(IC3-PE2(ADC6{slash}SS1)-Pad19)") (class "Default")
      (node (ref "IC3") (pin "19") (pinfunction "PE2(ADC6/SS1)_19") (pintype "bidirectional"))
    )
    (net (code "52") (name "unconnected-(SPI-NA1-Pad7)") (class "Default")
      (node (ref "SPI") (pin "7") (pinfunction "NA1_7") (pintype "bidirectional"))
    )
    (net (code "53") (name "unconnected-(SPI-NTRST-Pad8)") (class "Default")
      (node (ref "SPI") (pin "8") (pinfunction "NTRST_8") (pintype "bidirectional"))
    )
    (net (code "54") (name "unconnected-(SPI-TMS-Pad5)") (class "Default")
      (node (ref "SPI") (pin "5") (pinfunction "TMS_5") (pintype "bidirectional"))
    )
    (net (code "55") (name "unconnected-(U$1-PadSC1)") (class "Default")
      (node (ref "U$1") (pin "SC1") (pinfunction "SC1_SC1") (pintype "bidirectional"))
    )
    (net (code "56") (name "unconnected-(U$1-PadSC2)") (class "Default")
      (node (ref "U$1") (pin "SC2") (pinfunction "SC2_SC2") (pintype "bidirectional"))
    )
    (net (code "57") (name "unconnected-(U$1-PadSC3)") (class "Default")
      (node (ref "U$1") (pin "SC3") (pinfunction "SC3_SC3") (pintype "bidirectional"))
    )
    (net (code "58") (name "unconnected-(U$1-PadSC4)") (class "Default")
      (node (ref "U$1") (pin "SC4") (pinfunction "SC4_SC4") (pintype "bidirectional"))
    )
  )
)
